# slave.net
KiCad netlist of a schematic drawn in EAGLE
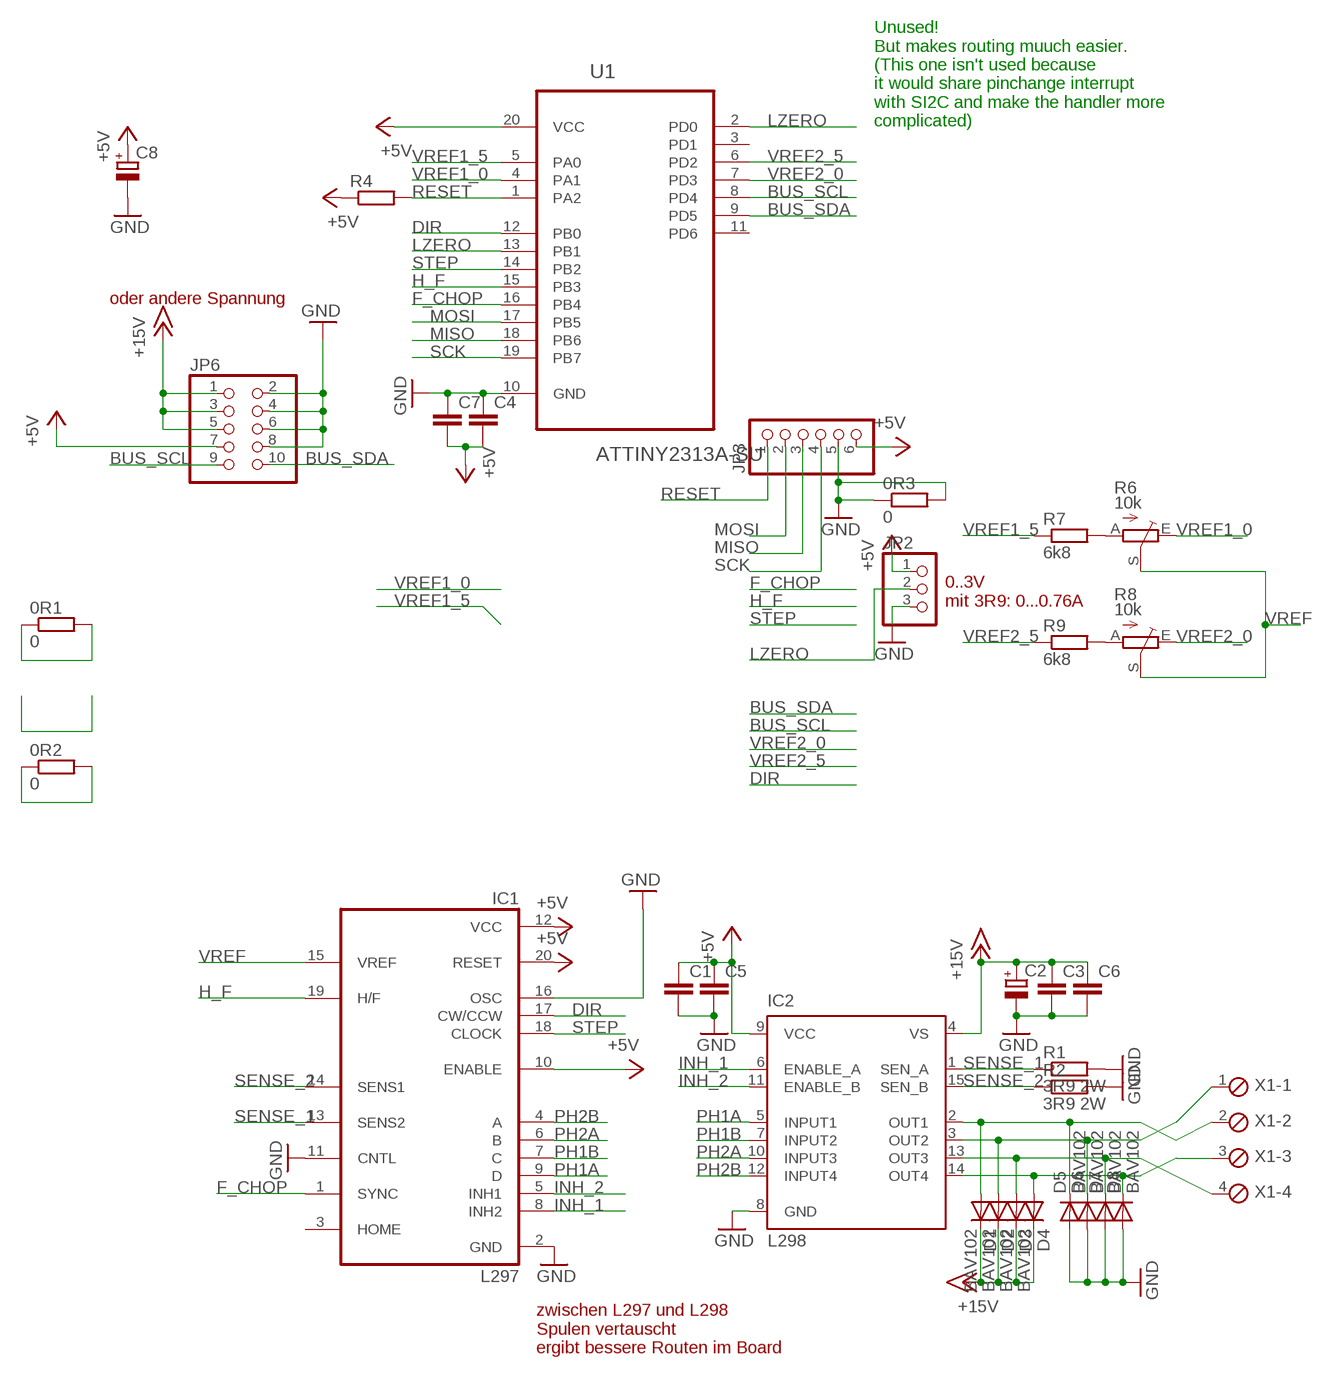
[diagram p0: schematic, sheet 1]

(export (version "E")
  (design (tool "Eeschema 10.0.6"))
  (components
    (comp (ref "0R1")
      (value "0")
      (footprint "eagle-import:R1206")
      (libsource (lib "eagle-import") (part "R-EU_R1206"))
    )
    (comp (ref "0R2")
      (value "0")
      (footprint "eagle-import:R1206")
      (libsource (lib "eagle-import") (part "R-EU_R1206"))
    )
    (comp (ref "0R3")
      (value "0")
      (footprint "eagle-import:R1206")
      (libsource (lib "eagle-import") (part "R-EU_R1206"))
    )
    (comp (ref "C1")
      (value "C-EUC0805")
      (footprint "eagle-import:C0805")
      (libsource (lib "eagle-import") (part "C-EUC0805"))
    )
    (comp (ref "C2")
      (value "CPOL-EUE2.5-7")
      (footprint "eagle-import:E2,5-7")
      (libsource (lib "eagle-import") (part "CPOL-EUE2.5-7"))
    )
    (comp (ref "C3")
      (value "C-EUC0805")
      (footprint "eagle-import:C0805")
      (libsource (lib "eagle-import") (part "C-EUC0805"))
    )
    (comp (ref "C4")
      (value "C-EUC0805")
      (footprint "eagle-import:C0805")
      (libsource (lib "eagle-import") (part "C-EUC0805"))
    )
    (comp (ref "C5")
      (value "C-EUC0805")
      (footprint "eagle-import:C0805")
      (libsource (lib "eagle-import") (part "C-EUC0805"))
    )
    (comp (ref "C6")
      (value "C-EUC0805")
      (footprint "eagle-import:C0805")
      (libsource (lib "eagle-import") (part "C-EUC0805"))
    )
    (comp (ref "C7")
      (value "C-EUC0805")
      (footprint "eagle-import:C0805")
      (libsource (lib "eagle-import") (part "C-EUC0805"))
    )
    (comp (ref "C8")
      (value "CPOL-EUE2.5-7")
      (footprint "eagle-import:E2,5-7")
      (libsource (lib "eagle-import") (part "CPOL-EUE2.5-7"))
    )
    (comp (ref "D1")
      (value "BAV102")
      (footprint "eagle-import:MINIMELF")
      (libsource (lib "eagle-import") (part "DIODE-MINIMELF"))
    )
    (comp (ref "D2")
      (value "BAV102")
      (footprint "eagle-import:MINIMELF")
      (libsource (lib "eagle-import") (part "DIODE-MINIMELF"))
    )
    (comp (ref "D3")
      (value "BAV102")
      (footprint "eagle-import:MINIMELF")
      (libsource (lib "eagle-import") (part "DIODE-MINIMELF"))
    )
    (comp (ref "D4")
      (value "BAV102")
      (footprint "eagle-import:MINIMELF")
      (libsource (lib "eagle-import") (part "DIODE-MINIMELF"))
    )
    (comp (ref "D5")
      (value "BAV102")
      (footprint "eagle-import:MINIMELF")
      (libsource (lib "eagle-import") (part "DIODE-MINIMELF"))
    )
    (comp (ref "D6")
      (value "BAV102")
      (footprint "eagle-import:MINIMELF")
      (libsource (lib "eagle-import") (part "DIODE-MINIMELF"))
    )
    (comp (ref "D7")
      (value "BAV102")
      (footprint "eagle-import:MINIMELF")
      (libsource (lib "eagle-import") (part "DIODE-MINIMELF"))
    )
    (comp (ref "D8")
      (value "BAV102")
      (footprint "eagle-import:MINIMELF")
      (libsource (lib "eagle-import") (part "DIODE-MINIMELF"))
    )
    (comp (ref "IC1")
      (value "L297")
      (footprint "eagle-import:DIL20")
      (fields (field (name "MPN") "L297/1"))
      (libsource (lib "eagle-import") (part "L297"))
    )
    (comp (ref "IC2")
      (value "L298")
      (footprint "eagle-import:MULTIWATT-15")
      (fields (field (name "MPN") "L298N"))
      (libsource (lib "eagle-import") (part "L298"))
    )
    (comp (ref "JP2")
      (value "PINHD-1X3")
      (footprint "eagle-import:1X03")
      (libsource (lib "eagle-import") (part "PINHD-1X3"))
    )
    (comp (ref "JP3")
      (value "PINHD-1X6")
      (footprint "eagle-import:1X06")
      (libsource (lib "eagle-import") (part "PINHD-1X6"))
    )
    (comp (ref "JP6")
      (value "PINHD-2X5")
      (footprint "eagle-import:2X05")
      (libsource (lib "eagle-import") (part "PINHD-2X5"))
    )
    (comp (ref "R1")
      (value "3R9 2W")
      (footprint "eagle-import:0414_15")
      (libsource (lib "eagle-import") (part "R-EU_0414/15"))
    )
    (comp (ref "R2")
      (value "3R9 2W")
      (footprint "eagle-import:0414_15")
      (libsource (lib "eagle-import") (part "R-EU_0414/15"))
    )
    (comp (ref "R4")
      (value "R-EU_R1206")
      (footprint "eagle-import:R1206")
      (libsource (lib "eagle-import") (part "R-EU_R1206"))
    )
    (comp (ref "R6")
      (value "10k")
      (footprint "eagle-import:PT-10")
      (libsource (lib "eagle-import") (part "TRIM_EU-PT10"))
    )
    (comp (ref "R7")
      (value "6k8")
      (footprint "eagle-import:R1206")
      (libsource (lib "eagle-import") (part "R-EU_R1206"))
    )
    (comp (ref "R8")
      (value "10k")
      (footprint "eagle-import:PT-10")
      (libsource (lib "eagle-import") (part "TRIM_EU-PT10"))
    )
    (comp (ref "R9")
      (value "6k8")
      (footprint "eagle-import:R1206")
      (libsource (lib "eagle-import") (part "R-EU_R1206"))
    )
    (comp (ref "U1")
      (value "ATTINY2313A-SU")
      (footprint "eagle-import:SOIC127P1032X265-20N")
      (libsource (lib "eagle-import") (part "ATTINY2313A-SU"))
    )
    (comp (ref "X1")
      (value "MPT4")
      (footprint "eagle-import:4POL254")
      (libsource (lib "eagle-import") (part "MPT4"))
    )
  )
  (nets
    (net (code "1") (name "+5V") (class "Default")
      (node (ref "0R1") (pin "1") (pinfunction "1_1") (pintype "passive"))
      (node (ref "0R1") (pin "2") (pinfunction "2_2") (pintype "passive"))
      (node (ref "C1") (pin "1") (pinfunction "1_1") (pintype "passive"))
      (node (ref "C4") (pin "2") (pinfunction "2_2") (pintype "passive"))
      (node (ref "C5") (pin "1") (pinfunction "1_1") (pintype "passive"))
      (node (ref "C7") (pin "2") (pinfunction "2_2") (pintype "passive"))
      (node (ref "C8") (pin "+") (pinfunction "+_+") (pintype "passive"))
      (node (ref "IC1") (pin "10") (pinfunction "ENABLE_10") (pintype "input"))
      (node (ref "IC1") (pin "12") (pinfunction "VCC_12") (pintype "power_in"))
      (node (ref "IC1") (pin "20") (pinfunction "RESET_20") (pintype "input"))
      (node (ref "IC2") (pin "9") (pinfunction "VCC_9") (pintype "power_in"))
      (node (ref "JP2") (pin "1") (pinfunction "1_1") (pintype "passive"))
      (node (ref "JP3") (pin "6") (pinfunction "6_6") (pintype "passive"))
      (node (ref "JP6") (pin "7") (pinfunction "7_7") (pintype "passive"))
      (node (ref "R4") (pin "1") (pinfunction "1_1") (pintype "passive"))
      (node (ref "U1") (pin "20") (pinfunction "VCC_20") (pintype "power_in"))
    )
    (net (code "2") (name "+15V") (class "Default")
      (node (ref "C2") (pin "+") (pinfunction "+_+") (pintype "passive"))
      (node (ref "C3") (pin "1") (pinfunction "1_1") (pintype "passive"))
      (node (ref "C6") (pin "1") (pinfunction "1_1") (pintype "passive"))
      (node (ref "D1") (pin "C") (pinfunction "C_C") (pintype "passive"))
      (node (ref "D2") (pin "C") (pinfunction "C_C") (pintype "passive"))
      (node (ref "D3") (pin "C") (pinfunction "C_C") (pintype "passive"))
      (node (ref "D4") (pin "C") (pinfunction "C_C") (pintype "passive"))
      (node (ref "IC2") (pin "4") (pinfunction "VS_4") (pintype "power_in"))
      (node (ref "JP6") (pin "1") (pinfunction "1_1") (pintype "passive"))
      (node (ref "JP6") (pin "3") (pinfunction "3_3") (pintype "passive"))
      (node (ref "JP6") (pin "5") (pinfunction "5_5") (pintype "passive"))
    )
    (net (code "3") (name "/BUS_SCL") (class "Default")
      (node (ref "JP6") (pin "9") (pinfunction "9_9") (pintype "passive"))
      (node (ref "U1") (pin "8") (pinfunction "PD4_8") (pintype "bidirectional"))
    )
    (net (code "4") (name "/BUS_SDA") (class "Default")
      (node (ref "JP6") (pin "10") (pinfunction "10_10") (pintype "passive"))
      (node (ref "U1") (pin "9") (pinfunction "PD5_9") (pintype "bidirectional"))
    )
    (net (code "5") (name "/DIR") (class "Default")
      (node (ref "IC1") (pin "17") (pinfunction "CW/CCW_17") (pintype "input"))
      (node (ref "U1") (pin "12") (pinfunction "PB0_12") (pintype "bidirectional"))
    )
    (net (code "6") (name "/F_CHOP") (class "Default")
      (node (ref "IC1") (pin "1") (pinfunction "SYNC_1") (pintype "output"))
      (node (ref "U1") (pin "16") (pinfunction "PB4_16") (pintype "bidirectional"))
    )
    (net (code "7") (name "/H_F") (class "Default")
      (node (ref "IC1") (pin "19") (pinfunction "H/F_19") (pintype "input"))
      (node (ref "U1") (pin "15") (pinfunction "PB3_15") (pintype "bidirectional"))
    )
    (net (code "8") (name "/INH_1") (class "Default")
      (node (ref "IC1") (pin "8") (pinfunction "INH2_8") (pintype "output"))
      (node (ref "IC2") (pin "6") (pinfunction "ENABLE_A_6") (pintype "input"))
    )
    (net (code "9") (name "/INH_2") (class "Default")
      (node (ref "IC1") (pin "5") (pinfunction "INH1_5") (pintype "output"))
      (node (ref "IC2") (pin "11") (pinfunction "ENABLE_B_11") (pintype "input"))
    )
    (net (code "10") (name "/LZERO") (class "Default")
      (node (ref "JP2") (pin "2") (pinfunction "2_2") (pintype "passive"))
      (node (ref "U1") (pin "13") (pinfunction "PB1_13") (pintype "bidirectional"))
      (node (ref "U1") (pin "2") (pinfunction "PD0_2") (pintype "bidirectional"))
    )
    (net (code "11") (name "/MISO") (class "Default")
      (node (ref "JP3") (pin "3") (pinfunction "3_3") (pintype "passive"))
      (node (ref "U1") (pin "18") (pinfunction "PB6_18") (pintype "bidirectional"))
    )
    (net (code "12") (name "/MOSI") (class "Default")
      (node (ref "JP3") (pin "2") (pinfunction "2_2") (pintype "passive"))
      (node (ref "U1") (pin "17") (pinfunction "PB5_17") (pintype "bidirectional"))
    )
    (net (code "13") (name "/PH1A") (class "Default")
      (node (ref "IC1") (pin "9") (pinfunction "D_9") (pintype "output"))
      (node (ref "IC2") (pin "5") (pinfunction "INPUT1_5") (pintype "input"))
    )
    (net (code "14") (name "/PH1B") (class "Default")
      (node (ref "IC1") (pin "7") (pinfunction "C_7") (pintype "output"))
      (node (ref "IC2") (pin "7") (pinfunction "INPUT2_7") (pintype "input"))
    )
    (net (code "15") (name "/PH2A") (class "Default")
      (node (ref "IC1") (pin "6") (pinfunction "B_6") (pintype "output"))
      (node (ref "IC2") (pin "10") (pinfunction "INPUT3_10") (pintype "input"))
    )
    (net (code "16") (name "/PH2B") (class "Default")
      (node (ref "IC1") (pin "4") (pinfunction "A_4") (pintype "output"))
      (node (ref "IC2") (pin "12") (pinfunction "INPUT4_12") (pintype "input"))
    )
    (net (code "17") (name "/RESET") (class "Default")
      (node (ref "JP3") (pin "1") (pinfunction "1_1") (pintype "passive"))
      (node (ref "R4") (pin "2") (pinfunction "2_2") (pintype "passive"))
      (node (ref "U1") (pin "1") (pinfunction "PA2_1") (pintype "bidirectional"))
    )
    (net (code "18") (name "/SCK") (class "Default")
      (node (ref "JP3") (pin "4") (pinfunction "4_4") (pintype "passive"))
      (node (ref "U1") (pin "19") (pinfunction "PB7_19") (pintype "bidirectional"))
    )
    (net (code "19") (name "/SENSE_1") (class "Default")
      (node (ref "IC1") (pin "13") (pinfunction "SENS2_13") (pintype "output"))
      (node (ref "IC2") (pin "1") (pinfunction "SEN_A_1") (pintype "input"))
      (node (ref "R1") (pin "1") (pinfunction "1_1") (pintype "passive"))
    )
    (net (code "20") (name "/SENSE_2") (class "Default")
      (node (ref "IC1") (pin "14") (pinfunction "SENS1_14") (pintype "output"))
      (node (ref "IC2") (pin "15") (pinfunction "SEN_B_15") (pintype "input"))
      (node (ref "R2") (pin "1") (pinfunction "1_1") (pintype "passive"))
    )
    (net (code "21") (name "/STEP") (class "Default")
      (node (ref "IC1") (pin "18") (pinfunction "CLOCK_18") (pintype "input"))
      (node (ref "U1") (pin "14") (pinfunction "PB2_14") (pintype "bidirectional"))
    )
    (net (code "22") (name "/VREF") (class "Default")
      (node (ref "0R2") (pin "1") (pinfunction "1_1") (pintype "passive"))
      (node (ref "0R2") (pin "2") (pinfunction "2_2") (pintype "passive"))
      (node (ref "IC1") (pin "15") (pinfunction "VREF_15") (pintype "input"))
      (node (ref "R6") (pin "S") (pinfunction "S_S") (pintype "passive"))
      (node (ref "R8") (pin "S") (pinfunction "S_S") (pintype "passive"))
    )
    (net (code "23") (name "/VREF1_0") (class "Default")
      (node (ref "R6") (pin "E") (pinfunction "E_E") (pintype "passive"))
      (node (ref "U1") (pin "4") (pinfunction "PA1_4") (pintype "bidirectional"))
    )
    (net (code "24") (name "/VREF1_5") (class "Default")
      (node (ref "R7") (pin "1") (pinfunction "1_1") (pintype "passive"))
      (node (ref "U1") (pin "5") (pinfunction "PA0_5") (pintype "bidirectional"))
    )
    (net (code "25") (name "/VREF2_0") (class "Default")
      (node (ref "R8") (pin "E") (pinfunction "E_E") (pintype "passive"))
      (node (ref "U1") (pin "7") (pinfunction "PD3_7") (pintype "bidirectional"))
    )
    (net (code "26") (name "/VREF2_5") (class "Default")
      (node (ref "R9") (pin "1") (pinfunction "1_1") (pintype "passive"))
      (node (ref "U1") (pin "6") (pinfunction "PD2_6") (pintype "bidirectional"))
    )
    (net (code "27") (name "GND") (class "Default")
      (node (ref "0R3") (pin "1") (pinfunction "1_1") (pintype "passive"))
      (node (ref "0R3") (pin "2") (pinfunction "2_2") (pintype "passive"))
      (node (ref "C1") (pin "2") (pinfunction "2_2") (pintype "passive"))
      (node (ref "C2") (pin "-") (pinfunction "-_-") (pintype "passive"))
      (node (ref "C3") (pin "2") (pinfunction "2_2") (pintype "passive"))
      (node (ref "C4") (pin "1") (pinfunction "1_1") (pintype "passive"))
      (node (ref "C5") (pin "2") (pinfunction "2_2") (pintype "passive"))
      (node (ref "C6") (pin "2") (pinfunction "2_2") (pintype "passive"))
      (node (ref "C7") (pin "1") (pinfunction "1_1") (pintype "passive"))
      (node (ref "C8") (pin "-") (pinfunction "-_-") (pintype "passive"))
      (node (ref "D5") (pin "A") (pinfunction "A_A") (pintype "passive"))
      (node (ref "D6") (pin "A") (pinfunction "A_A") (pintype "passive"))
      (node (ref "D7") (pin "A") (pinfunction "A_A") (pintype "passive"))
      (node (ref "D8") (pin "A") (pinfunction "A_A") (pintype "passive"))
      (node (ref "IC1") (pin "11") (pinfunction "CNTL_11") (pintype "input"))
      (node (ref "IC1") (pin "16") (pinfunction "OSC_16") (pintype "bidirectional"))
      (node (ref "IC1") (pin "2") (pinfunction "GND_2") (pintype "power_in"))
      (node (ref "IC2") (pin "8") (pinfunction "GND_8") (pintype "power_in"))
      (node (ref "JP2") (pin "3") (pinfunction "3_3") (pintype "passive"))
      (node (ref "JP3") (pin "5") (pinfunction "5_5") (pintype "passive"))
      (node (ref "JP6") (pin "2") (pinfunction "2_2") (pintype "passive"))
      (node (ref "JP6") (pin "4") (pinfunction "4_4") (pintype "passive"))
      (node (ref "JP6") (pin "6") (pinfunction "6_6") (pintype "passive"))
      (node (ref "JP6") (pin "8") (pinfunction "8_8") (pintype "passive"))
      (node (ref "R1") (pin "2") (pinfunction "2_2") (pintype "passive"))
      (node (ref "R2") (pin "2") (pinfunction "2_2") (pintype "passive"))
      (node (ref "U1") (pin "10") (pinfunction "GND_10") (pintype "passive"))
    )
    (net (code "28") (name "Net-(IC2-OUT1)") (class "Default")
      (node (ref "D1") (pin "A") (pinfunction "A_A") (pintype "passive"))
      (node (ref "D5") (pin "C") (pinfunction "C_C") (pintype "passive"))
      (node (ref "IC2") (pin "2") (pinfunction "OUT1_2") (pintype "output"))
      (node (ref "X1") (pin "2") (pinfunction "1_2") (pintype "passive"))
    )
    (net (code "29") (name "Net-(IC2-OUT2)") (class "Default")
      (node (ref "D2") (pin "A") (pinfunction "A_A") (pintype "passive"))
      (node (ref "D6") (pin "C") (pinfunction "C_C") (pintype "passive"))
      (node (ref "IC2") (pin "3") (pinfunction "OUT2_3") (pintype "output"))
      (node (ref "X1") (pin "1") (pinfunction "1_1") (pintype "passive"))
    )
    (net (code "30") (name "Net-(IC2-OUT3)") (class "Default")
      (node (ref "D3") (pin "A") (pinfunction "A_A") (pintype "passive"))
      (node (ref "D7") (pin "C") (pinfunction "C_C") (pintype "passive"))
      (node (ref "IC2") (pin "13") (pinfunction "OUT3_13") (pintype "output"))
      (node (ref "X1") (pin "4") (pinfunction "1_4") (pintype "passive"))
    )
    (net (code "31") (name "Net-(IC2-OUT4)") (class "Default")
      (node (ref "D4") (pin "A") (pinfunction "A_A") (pintype "passive"))
      (node (ref "D8") (pin "C") (pinfunction "C_C") (pintype "passive"))
      (node (ref "IC2") (pin "14") (pinfunction "OUT4_14") (pintype "output"))
      (node (ref "X1") (pin "3") (pinfunction "1_3") (pintype "passive"))
    )
    (net (code "32") (name "Net-(R6-PadA)") (class "Default")
      (node (ref "R6") (pin "A") (pinfunction "A_A") (pintype "passive"))
      (node (ref "R7") (pin "2") (pinfunction "2_2") (pintype "passive"))
    )
    (net (code "33") (name "Net-(R8-PadA)") (class "Default")
      (node (ref "R8") (pin "A") (pinfunction "A_A") (pintype "passive"))
      (node (ref "R9") (pin "2") (pinfunction "2_2") (pintype "passive"))
    )
    (net (code "34") (name "unconnected-(IC1-HOME-Pad3)") (class "Default")
      (node (ref "IC1") (pin "3") (pinfunction "HOME_3") (pintype "output"))
    )
    (net (code "35") (name "unconnected-(U1-PD1-Pad3)") (class "Default")
      (node (ref "U1") (pin "3") (pinfunction "PD1_3") (pintype "bidirectional"))
    )
    (net (code "36") (name "unconnected-(U1-PD6-Pad11)") (class "Default")
      (node (ref "U1") (pin "11") (pinfunction "PD6_11") (pintype "bidirectional"))
    )
  )
)
